# design.net
KiCad netlist of a schematic drawn in Altium Designer
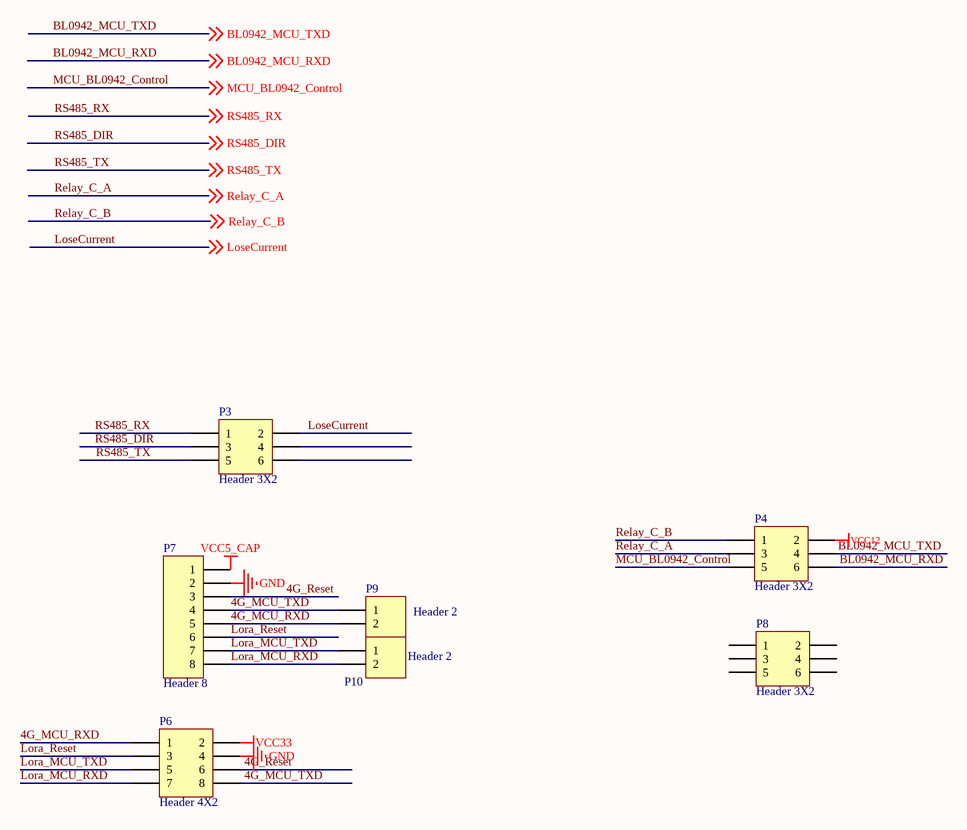
[diagram p0: 连接.SchDoc]

(export (version "E")
  (design (tool "Eeschema 10.0.6"))
  (components
    (comp (ref "P3")
      (value "Header 3X2")
      (footprint "CONN-SMD_5BME8-08872-203-W0")
      (description "Header, 3-Pin, Dual row")
      (fields (field (name "PUBLISHER") "Altium Limited"))
      (libsource (lib "Miscellaneous Connectors") (part "Header 3X2"))
    )
    (comp (ref "P4")
      (value "Header 3X2")
      (footprint "CONN-SMD_5BME8-08872-203-W0")
      (description "Header, 3-Pin, Dual row")
      (fields (field (name "PUBLISHER") "Altium Limited"))
      (libsource (lib "Miscellaneous Connectors") (part "Header 3X2"))
    )
    (comp (ref "P6")
      (value "Header 4X2")
      (footprint "CONN-SMD_5BME8-08872-204-W0")
      (description "Header, 4-Pin, Dual row")
      (fields (field (name "PUBLISHER") "Altium Limited"))
      (libsource (lib "Miscellaneous Connectors") (part "Header 4X2"))
    )
    (comp (ref "P7")
      (value "Header 8")
      (footprint "HDR1X8")
      (description "Header, 8-Pin")
      (fields (field (name "PUBLISHER") "Altium Limited"))
      (libsource (lib "Miscellaneous Connectors") (part "Header 8"))
    )
    (comp (ref "P8")
      (value "Header 3X2")
      (footprint "CONN-SMD_5BME8-08872-203-W0")
      (description "Header, 3-Pin, Dual row")
      (fields (field (name "PUBLISHER") "Altium Limited"))
      (libsource (lib "Miscellaneous Connectors") (part "Header 3X2"))
    )
    (comp (ref "P9")
      (value "Header 2")
      (footprint "HDR1X2")
      (description "Header, 2-Pin")
      (fields (field (name "PUBLISHER") "Altium Limited"))
      (libsource (lib "Miscellaneous Connectors") (part "Header 2"))
    )
    (comp (ref "P10")
      (value "Header 2")
      (footprint "HDR1X2")
      (description "Header, 2-Pin")
      (fields (field (name "PUBLISHER") "Altium Limited"))
      (libsource (lib "Miscellaneous Connectors") (part "Header 2"))
    )
  )
  (nets
    (net (code "1") (name "/4G_MCU_RXD") (class "Default")
      (node (ref "P6") (pin "1") (pinfunction "1_1") (pintype "passive"))
      (node (ref "P7") (pin "5") (pinfunction "5_5") (pintype "passive"))
      (node (ref "P9") (pin "2") (pinfunction "2_2") (pintype "passive"))
    )
    (net (code "2") (name "/4G_MCU_TXD") (class "Default")
      (node (ref "P6") (pin "8") (pinfunction "8_8") (pintype "passive"))
      (node (ref "P7") (pin "4") (pinfunction "4_4") (pintype "passive"))
      (node (ref "P9") (pin "1") (pinfunction "1_1") (pintype "passive"))
    )
    (net (code "3") (name "/4G_Reset") (class "Default")
      (node (ref "P6") (pin "6") (pinfunction "6_6") (pintype "passive"))
      (node (ref "P7") (pin "3") (pinfunction "3_3") (pintype "passive"))
    )
    (net (code "4") (name "/Lora_MCU_RXD") (class "Default")
      (node (ref "P10") (pin "2") (pinfunction "2_2") (pintype "passive"))
      (node (ref "P6") (pin "7") (pinfunction "7_7") (pintype "passive"))
      (node (ref "P7") (pin "8") (pinfunction "8_8") (pintype "passive"))
    )
    (net (code "5") (name "/Lora_MCU_TXD") (class "Default")
      (node (ref "P10") (pin "1") (pinfunction "1_1") (pintype "passive"))
      (node (ref "P6") (pin "5") (pinfunction "5_5") (pintype "passive"))
      (node (ref "P7") (pin "7") (pinfunction "7_7") (pintype "passive"))
    )
    (net (code "6") (name "/Lora_Reset") (class "Default")
      (node (ref "P6") (pin "3") (pinfunction "3_3") (pintype "passive"))
      (node (ref "P7") (pin "6") (pinfunction "6_6") (pintype "passive"))
    )
    (net (code "7") (name "BL0942_MCU_RXD") (class "Default")
      (node (ref "P4") (pin "6") (pinfunction "6_6") (pintype "passive"))
    )
    (net (code "8") (name "BL0942_MCU_TXD") (class "Default")
      (node (ref "P4") (pin "4") (pinfunction "4_4") (pintype "passive"))
    )
    (net (code "9") (name "GND") (class "Default")
      (node (ref "P6") (pin "4") (pinfunction "4_4") (pintype "passive"))
      (node (ref "P7") (pin "2") (pinfunction "2_2") (pintype "passive"))
    )
    (net (code "10") (name "LoseCurrent") (class "Default")
      (node (ref "P3") (pin "2") (pinfunction "2_2") (pintype "passive"))
    )
    (net (code "11") (name "MCU_BL0942_Control") (class "Default")
      (node (ref "P4") (pin "5") (pinfunction "5_5") (pintype "passive"))
    )
    (net (code "12") (name "RS485_DIR") (class "Default")
      (node (ref "P3") (pin "3") (pinfunction "3_3") (pintype "passive"))
    )
    (net (code "13") (name "RS485_RX") (class "Default")
      (node (ref "P3") (pin "1") (pinfunction "1_1") (pintype "passive"))
    )
    (net (code "14") (name "RS485_TX") (class "Default")
      (node (ref "P3") (pin "5") (pinfunction "5_5") (pintype "passive"))
    )
    (net (code "15") (name "Relay_C_A") (class "Default")
      (node (ref "P4") (pin "3") (pinfunction "3_3") (pintype "passive"))
    )
    (net (code "16") (name "Relay_C_B") (class "Default")
      (node (ref "P4") (pin "1") (pinfunction "1_1") (pintype "passive"))
    )
    (net (code "17") (name "VCC5_CAP") (class "Default")
      (node (ref "P7") (pin "1") (pinfunction "1_1") (pintype "passive"))
    )
    (net (code "18") (name "VCC12") (class "Default")
      (node (ref "P4") (pin "2") (pinfunction "2_2") (pintype "passive"))
    )
    (net (code "19") (name "VCC33") (class "Default")
      (node (ref "P6") (pin "2") (pinfunction "2_2") (pintype "passive"))
    )
    (net (code "20") (name "unconnected-(P3-Pad4)") (class "Default")
      (node (ref "P3") (pin "4") (pinfunction "4_4") (pintype "passive"))
    )
    (net (code "21") (name "unconnected-(P3-Pad6)") (class "Default")
      (node (ref "P3") (pin "6") (pinfunction "6_6") (pintype "passive"))
    )
    (net (code "22") (name "unconnected-(P8-Pad1)") (class "Default")
      (node (ref "P8") (pin "1") (pinfunction "1_1") (pintype "passive"))
    )
    (net (code "23") (name "unconnected-(P8-Pad2)") (class "Default")
      (node (ref "P8") (pin "2") (pinfunction "2_2") (pintype "passive"))
    )
    (net (code "24") (name "unconnected-(P8-Pad3)") (class "Default")
      (node (ref "P8") (pin "3") (pinfunction "3_3") (pintype "passive"))
    )
    (net (code "25") (name "unconnected-(P8-Pad4)") (class "Default")
      (node (ref "P8") (pin "4") (pinfunction "4_4") (pintype "passive"))
    )
    (net (code "26") (name "unconnected-(P8-Pad5)") (class "Default")
      (node (ref "P8") (pin "5") (pinfunction "5_5") (pintype "passive"))
    )
    (net (code "27") (name "unconnected-(P8-Pad6)") (class "Default")
      (node (ref "P8") (pin "6") (pinfunction "6_6") (pintype "passive"))
    )
  )
)
